# femto.net
KiCad netlist of a schematic drawn in EAGLE
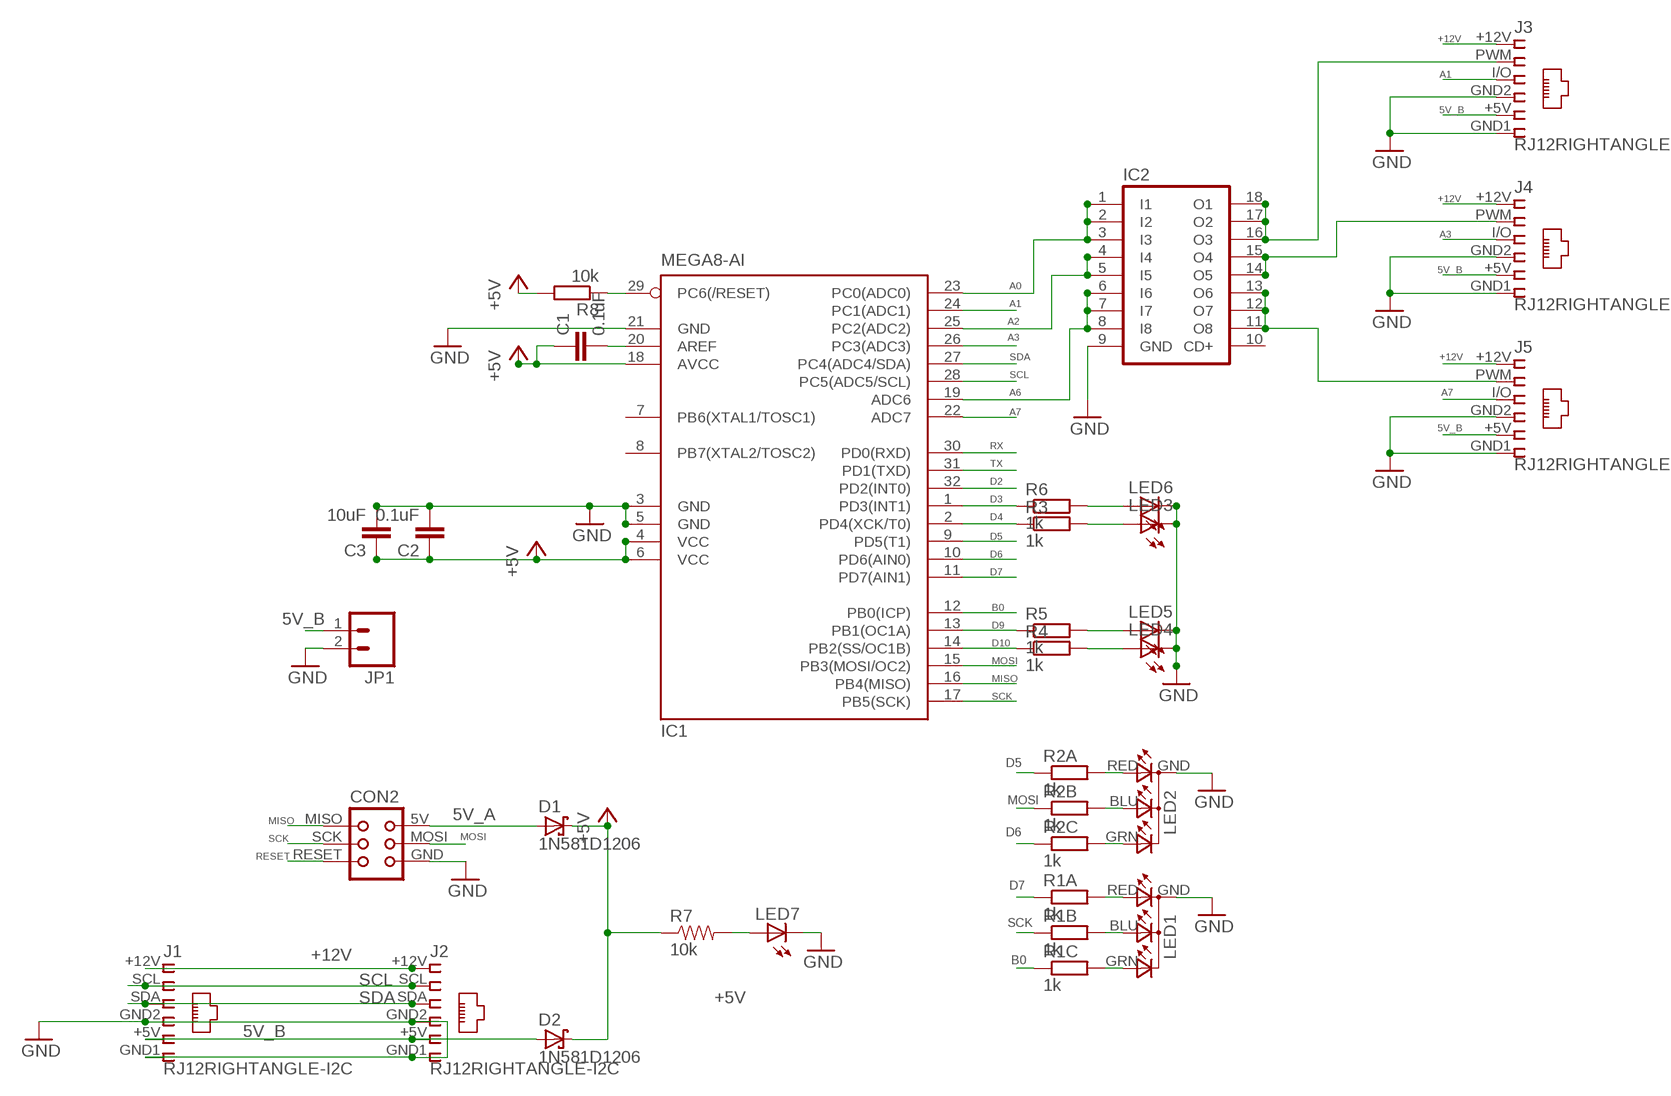
[diagram p0: schematic, sheet 1]

(export (version "E")
  (design (tool "Eeschema 10.0.6"))
  (components
    (comp (ref "C1")
      (value "0.1uF")
      (footprint "eagle-import:C1206")
      (libsource (lib "eagle-import") (part "C-EUC1206"))
    )
    (comp (ref "C2")
      (value "0.1uF")
      (footprint "eagle-import:C1206")
      (libsource (lib "eagle-import") (part "C-EUC1206"))
    )
    (comp (ref "C3")
      (value "10uF")
      (footprint "eagle-import:C1206")
      (libsource (lib "eagle-import") (part "C-EUC1206"))
    )
    (comp (ref "CON2")
      (value "TINYISPTAG")
      (footprint "eagle-import:TC2030-MCP")
      (libsource (lib "eagle-import") (part "TINYISPTAG"))
    )
    (comp (ref "D1")
      (value "1N581D1206")
      (footprint "eagle-import:LED-1206")
      (libsource (lib "eagle-import") (part "1N581D1206"))
    )
    (comp (ref "D2")
      (value "1N581D1206")
      (footprint "eagle-import:LED-1206")
      (libsource (lib "eagle-import") (part "1N581D1206"))
    )
    (comp (ref "IC1")
      (value "MEGA8-AI")
      (footprint "eagle-import:TQFP32-08")
      (fields (field (name "MPN") "ATMEGA8-16AU"))
      (libsource (lib "eagle-import") (part "MEGA8-AI"))
    )
    (comp (ref "IC2")
      (value "ULN2803A")
      (footprint "eagle-import:SO18W")
      (libsource (lib "eagle-import") (part "ULN2803A"))
    )
    (comp (ref "J1")
      (value "RJ12RIGHTANGLE-I2C")
      (footprint "eagle-import:RJ12-RIGHTANGLE-I2C")
      (libsource (lib "eagle-import") (part "RJ12RIGHTANGLE-I2C"))
    )
    (comp (ref "J2")
      (value "RJ12RIGHTANGLE-I2C")
      (footprint "eagle-import:RJ12-RIGHTANGLE-I2C")
      (libsource (lib "eagle-import") (part "RJ12RIGHTANGLE-I2C"))
    )
    (comp (ref "J3")
      (value "RJ12RIGHTANGLE")
      (footprint "eagle-import:RJ12-RIGHTANGLE")
      (libsource (lib "eagle-import") (part "RJ12RIGHTANGLE"))
    )
    (comp (ref "J4")
      (value "RJ12RIGHTANGLE")
      (footprint "eagle-import:RJ12-RIGHTANGLE")
      (libsource (lib "eagle-import") (part "RJ12RIGHTANGLE"))
    )
    (comp (ref "J5")
      (value "RJ12RIGHTANGLE")
      (footprint "eagle-import:RJ12-RIGHTANGLE")
      (libsource (lib "eagle-import") (part "RJ12RIGHTANGLE"))
    )
    (comp (ref "JP1")
      (value "M023.5MM")
      (footprint "eagle-import:SCREWTERMINAL-3.5MM-2")
      (libsource (lib "eagle-import") (part "M023.5MM"))
    )
    (comp (ref "LED1")
      (value "RGB-COMMON-CATHODE")
      (footprint "eagle-import:LED-TRICOLOR-THROUGHHOLE")
      (libsource (lib "eagle-import") (part "RGB-COMMON-CATHODE"))
    )
    (comp (ref "LED2")
      (value "RGB-COMMON-CATHODE")
      (footprint "eagle-import:LED-TRICOLOR-THROUGHHOLE")
      (libsource (lib "eagle-import") (part "RGB-COMMON-CATHODE"))
    )
    (comp (ref "LED3")
      (value "LED3MM")
      (footprint "eagle-import:LED3MM")
      (libsource (lib "eagle-import") (part "lpatiny_LED3MM"))
    )
    (comp (ref "LED4")
      (value "LED3MM")
      (footprint "eagle-import:LED3MM")
      (libsource (lib "eagle-import") (part "lpatiny_LED3MM"))
    )
    (comp (ref "LED5")
      (value "LED3MM")
      (footprint "eagle-import:LED3MM")
      (libsource (lib "eagle-import") (part "lpatiny_LED3MM"))
    )
    (comp (ref "LED6")
      (value "LED3MM")
      (footprint "eagle-import:LED3MM")
      (libsource (lib "eagle-import") (part "lpatiny_LED3MM"))
    )
    (comp (ref "LED7")
      (value "LEDCHIP-LED0603")
      (footprint "eagle-import:CHIP-LED0603")
      (libsource (lib "eagle-import") (part "LEDCHIP-LED0603"))
    )
    (comp (ref "R1A")
      (value "1k")
      (footprint "eagle-import:M1206")
      (libsource (lib "eagle-import") (part "R-EU_M1206"))
    )
    (comp (ref "R1B")
      (value "1k")
      (footprint "eagle-import:M1206")
      (libsource (lib "eagle-import") (part "R-EU_M1206"))
    )
    (comp (ref "R1C")
      (value "1k")
      (footprint "eagle-import:M1206")
      (libsource (lib "eagle-import") (part "R-EU_M1206"))
    )
    (comp (ref "R2A")
      (value "1k")
      (footprint "eagle-import:M1206")
      (libsource (lib "eagle-import") (part "R-EU_M1206"))
    )
    (comp (ref "R2B")
      (value "1k")
      (footprint "eagle-import:M1206")
      (libsource (lib "eagle-import") (part "R-EU_M1206"))
    )
    (comp (ref "R2C")
      (value "1k")
      (footprint "eagle-import:M1206")
      (libsource (lib "eagle-import") (part "R-EU_M1206"))
    )
    (comp (ref "R3")
      (value "1k")
      (footprint "eagle-import:M1206")
      (libsource (lib "eagle-import") (part "R-EU_M1206"))
    )
    (comp (ref "R4")
      (value "1k")
      (footprint "eagle-import:M1206")
      (libsource (lib "eagle-import") (part "R-EU_M1206"))
    )
    (comp (ref "R5")
      (value "1k")
      (footprint "eagle-import:M1206")
      (libsource (lib "eagle-import") (part "R-EU_M1206"))
    )
    (comp (ref "R6")
      (value "1k")
      (footprint "eagle-import:M1206")
      (libsource (lib "eagle-import") (part "R-EU_M1206"))
    )
    (comp (ref "R7")
      (value "10k")
      (footprint "eagle-import:0603-RES")
      (libsource (lib "eagle-import") (part "RESISTOR0603-RES"))
    )
    (comp (ref "R8")
      (value "10k")
      (footprint "eagle-import:M1206")
      (libsource (lib "eagle-import") (part "R-EU_M1206"))
    )
  )
  (nets
    (net (code "1") (name "+5V") (class "Default")
      (node (ref "C1") (pin "1") (pinfunction "1_1") (pintype "passive"))
      (node (ref "C2") (pin "1") (pinfunction "1_1") (pintype "passive"))
      (node (ref "C3") (pin "1") (pinfunction "1_1") (pintype "passive"))
      (node (ref "D1") (pin "C") (pinfunction "C_C") (pintype "passive"))
      (node (ref "D2") (pin "C") (pinfunction "C_C") (pintype "passive"))
      (node (ref "IC1") (pin "18") (pinfunction "AVCC_18") (pintype "power_in"))
      (node (ref "IC1") (pin "4") (pinfunction "VCC_4") (pintype "power_in"))
      (node (ref "IC1") (pin "6") (pinfunction "VCC_6") (pintype "power_in"))
      (node (ref "R7") (pin "1") (pinfunction "1_1") (pintype "passive"))
      (node (ref "R8") (pin "2") (pinfunction "2_2") (pintype "passive"))
    )
    (net (code "2") (name "/+12V") (class "Default")
      (node (ref "J1") (pin "+12V") (pinfunction "1_+12V") (pintype "bidirectional"))
      (node (ref "J2") (pin "+12V") (pinfunction "1_+12V") (pintype "bidirectional"))
      (node (ref "J3") (pin "+12V") (pinfunction "1_+12V") (pintype "bidirectional"))
      (node (ref "J4") (pin "+12V") (pinfunction "1_+12V") (pintype "bidirectional"))
      (node (ref "J5") (pin "+12V") (pinfunction "1_+12V") (pintype "bidirectional"))
    )
    (net (code "3") (name "/5V_A") (class "Default")
      (node (ref "CON2") (pin "5V") (pinfunction "VCC_5V") (pintype "passive"))
      (node (ref "D1") (pin "A") (pinfunction "A_A") (pintype "passive"))
    )
    (net (code "4") (name "/5V_B") (class "Default")
      (node (ref "D2") (pin "A") (pinfunction "A_A") (pintype "passive"))
      (node (ref "J1") (pin "+5V") (pinfunction "5_+5V") (pintype "bidirectional"))
      (node (ref "J2") (pin "+5V") (pinfunction "5_+5V") (pintype "bidirectional"))
      (node (ref "J3") (pin "+5V") (pinfunction "5_+5V") (pintype "bidirectional"))
      (node (ref "J4") (pin "+5V") (pinfunction "5_+5V") (pintype "bidirectional"))
      (node (ref "J5") (pin "+5V") (pinfunction "5_+5V") (pintype "bidirectional"))
      (node (ref "JP1") (pin "1") (pinfunction "1_1") (pintype "passive"))
    )
    (net (code "5") (name "/A0") (class "Default")
      (node (ref "IC1") (pin "23") (pinfunction "PC0(ADC0)_23") (pintype "bidirectional"))
      (node (ref "IC2") (pin "1") (pinfunction "I1_1") (pintype "input"))
      (node (ref "IC2") (pin "2") (pinfunction "I2_2") (pintype "input"))
      (node (ref "IC2") (pin "3") (pinfunction "I3_3") (pintype "input"))
    )
    (net (code "6") (name "/A1") (class "Default")
      (node (ref "IC1") (pin "24") (pinfunction "PC1(ADC1)_24") (pintype "bidirectional"))
      (node (ref "J3") (pin "I/O") (pinfunction "3_I/O") (pintype "bidirectional"))
    )
    (net (code "7") (name "/A2") (class "Default")
      (node (ref "IC1") (pin "25") (pinfunction "PC2(ADC2)_25") (pintype "bidirectional"))
      (node (ref "IC2") (pin "4") (pinfunction "I4_4") (pintype "input"))
      (node (ref "IC2") (pin "5") (pinfunction "I5_5") (pintype "input"))
    )
    (net (code "8") (name "/A3") (class "Default")
      (node (ref "IC1") (pin "26") (pinfunction "PC3(ADC3)_26") (pintype "bidirectional"))
      (node (ref "J4") (pin "I/O") (pinfunction "3_I/O") (pintype "bidirectional"))
    )
    (net (code "9") (name "/A6") (class "Default")
      (node (ref "IC1") (pin "19") (pinfunction "ADC6_19") (pintype "bidirectional"))
      (node (ref "IC2") (pin "6") (pinfunction "I6_6") (pintype "input"))
      (node (ref "IC2") (pin "7") (pinfunction "I7_7") (pintype "input"))
      (node (ref "IC2") (pin "8") (pinfunction "I8_8") (pintype "input"))
    )
    (net (code "10") (name "/A7") (class "Default")
      (node (ref "IC1") (pin "22") (pinfunction "ADC7_22") (pintype "bidirectional"))
      (node (ref "J5") (pin "I/O") (pinfunction "3_I/O") (pintype "bidirectional"))
    )
    (net (code "11") (name "/B0") (class "Default")
      (node (ref "IC1") (pin "12") (pinfunction "PB0(ICP)_12") (pintype "bidirectional"))
      (node (ref "R1C") (pin "1") (pinfunction "1_1") (pintype "passive"))
    )
    (net (code "12") (name "/D2") (class "Default")
      (node (ref "IC1") (pin "32") (pinfunction "PD2(INT0)_32") (pintype "bidirectional"))
    )
    (net (code "13") (name "/D3") (class "Default")
      (node (ref "IC1") (pin "1") (pinfunction "PD3(INT1)_1") (pintype "bidirectional"))
      (node (ref "R6") (pin "1") (pinfunction "1_1") (pintype "passive"))
    )
    (net (code "14") (name "/D4") (class "Default")
      (node (ref "IC1") (pin "2") (pinfunction "PD4(XCK/T0)_2") (pintype "bidirectional"))
      (node (ref "R3") (pin "1") (pinfunction "1_1") (pintype "passive"))
    )
    (net (code "15") (name "/D5") (class "Default")
      (node (ref "IC1") (pin "9") (pinfunction "PD5(T1)_9") (pintype "bidirectional"))
      (node (ref "R2A") (pin "1") (pinfunction "1_1") (pintype "passive"))
    )
    (net (code "16") (name "/D6") (class "Default")
      (node (ref "IC1") (pin "10") (pinfunction "PD6(AIN0)_10") (pintype "bidirectional"))
      (node (ref "R2C") (pin "1") (pinfunction "1_1") (pintype "passive"))
    )
    (net (code "17") (name "/D7") (class "Default")
      (node (ref "IC1") (pin "11") (pinfunction "PD7(AIN1)_11") (pintype "bidirectional"))
      (node (ref "R1A") (pin "1") (pinfunction "1_1") (pintype "passive"))
    )
    (net (code "18") (name "/D9") (class "Default")
      (node (ref "IC1") (pin "13") (pinfunction "PB1(OC1A)_13") (pintype "bidirectional"))
      (node (ref "R5") (pin "1") (pinfunction "1_1") (pintype "passive"))
    )
    (net (code "19") (name "/D10") (class "Default")
      (node (ref "IC1") (pin "14") (pinfunction "PB2(SS/OC1B)_14") (pintype "bidirectional"))
      (node (ref "R4") (pin "1") (pinfunction "1_1") (pintype "passive"))
    )
    (net (code "20") (name "/MISO") (class "Default")
      (node (ref "CON2") (pin "MISO") (pinfunction "MISO_MISO") (pintype "passive"))
      (node (ref "IC1") (pin "16") (pinfunction "PB4(MISO)_16") (pintype "bidirectional"))
    )
    (net (code "21") (name "/MOSI") (class "Default")
      (node (ref "CON2") (pin "MOSI") (pinfunction "MOSI_MOSI") (pintype "passive"))
      (node (ref "IC1") (pin "15") (pinfunction "PB3(MOSI/OC2)_15") (pintype "bidirectional"))
      (node (ref "R2B") (pin "1") (pinfunction "1_1") (pintype "passive"))
    )
    (net (code "22") (name "/RESET") (class "Default")
      (node (ref "CON2") (pin "RESET") (pinfunction "RESET_RESET") (pintype "passive"))
      (node (ref "IC1") (pin "29") (pinfunction "PC6(/RESET)_29") (pintype "bidirectional"))
      (node (ref "R8") (pin "1") (pinfunction "1_1") (pintype "passive"))
    )
    (net (code "23") (name "/RX") (class "Default")
      (node (ref "IC1") (pin "30") (pinfunction "PD0(RXD)_30") (pintype "bidirectional"))
    )
    (net (code "24") (name "/SCK") (class "Default")
      (node (ref "CON2") (pin "SCK") (pinfunction "SCK_SCK") (pintype "passive"))
      (node (ref "IC1") (pin "17") (pinfunction "PB5(SCK)_17") (pintype "bidirectional"))
      (node (ref "R1B") (pin "1") (pinfunction "1_1") (pintype "passive"))
    )
    (net (code "25") (name "/SCL") (class "Default")
      (node (ref "IC1") (pin "28") (pinfunction "PC5(ADC5/SCL)_28") (pintype "bidirectional"))
      (node (ref "J1") (pin "SCL") (pinfunction "2_SCL") (pintype "bidirectional"))
      (node (ref "J2") (pin "SCL") (pinfunction "2_SCL") (pintype "bidirectional"))
    )
    (net (code "26") (name "/SDA") (class "Default")
      (node (ref "IC1") (pin "27") (pinfunction "PC4(ADC4/SDA)_27") (pintype "bidirectional"))
      (node (ref "J1") (pin "SDA") (pinfunction "3_SDA") (pintype "bidirectional"))
      (node (ref "J2") (pin "SDA") (pinfunction "3_SDA") (pintype "bidirectional"))
    )
    (net (code "27") (name "/TX") (class "Default")
      (node (ref "IC1") (pin "31") (pinfunction "PD1(TXD)_31") (pintype "bidirectional"))
    )
    (net (code "28") (name "GND") (class "Default")
      (node (ref "C2") (pin "2") (pinfunction "2_2") (pintype "passive"))
      (node (ref "C3") (pin "2") (pinfunction "2_2") (pintype "passive"))
      (node (ref "CON2") (pin "GND") (pinfunction "GND_GND") (pintype "passive"))
      (node (ref "IC1") (pin "21") (pinfunction "GND_21") (pintype "power_in"))
      (node (ref "IC1") (pin "3") (pinfunction "GND_3") (pintype "power_in"))
      (node (ref "IC1") (pin "5") (pinfunction "GND_5") (pintype "power_in"))
      (node (ref "IC2") (pin "9") (pinfunction "GND_9") (pintype "power_in"))
      (node (ref "J1") (pin "GND1") (pinfunction "6_GND1") (pintype "bidirectional"))
      (node (ref "J1") (pin "GND2") (pinfunction "4_GND2") (pintype "bidirectional"))
      (node (ref "J2") (pin "GND1") (pinfunction "6_GND1") (pintype "bidirectional"))
      (node (ref "J2") (pin "GND2") (pinfunction "4_GND2") (pintype "bidirectional"))
      (node (ref "J3") (pin "GND1") (pinfunction "6_GND1") (pintype "bidirectional"))
      (node (ref "J3") (pin "GND2") (pinfunction "4_GND2") (pintype "bidirectional"))
      (node (ref "J4") (pin "GND1") (pinfunction "6_GND1") (pintype "bidirectional"))
      (node (ref "J4") (pin "GND2") (pinfunction "4_GND2") (pintype "bidirectional"))
      (node (ref "J5") (pin "GND1") (pinfunction "6_GND1") (pintype "bidirectional"))
      (node (ref "J5") (pin "GND2") (pinfunction "4_GND2") (pintype "bidirectional"))
      (node (ref "JP1") (pin "2") (pinfunction "2_2") (pintype "passive"))
      (node (ref "LED1") (pin "GND") (pinfunction "A2_GND") (pintype "passive"))
      (node (ref "LED2") (pin "GND") (pinfunction "A2_GND") (pintype "passive"))
      (node (ref "LED3") (pin "K") (pinfunction "C_K") (pintype "passive"))
      (node (ref "LED4") (pin "K") (pinfunction "C_K") (pintype "passive"))
      (node (ref "LED5") (pin "K") (pinfunction "C_K") (pintype "passive"))
      (node (ref "LED6") (pin "K") (pinfunction "C_K") (pintype "passive"))
      (node (ref "LED7") (pin "C") (pinfunction "C_C") (pintype "passive"))
    )
    (net (code "29") (name "Net-(IC1-AREF)") (class "Default")
      (node (ref "C1") (pin "2") (pinfunction "2_2") (pintype "passive"))
      (node (ref "IC1") (pin "20") (pinfunction "AREF_20") (pintype "passive"))
    )
    (net (code "30") (name "Net-(IC2-O1)") (class "Default")
      (node (ref "IC2") (pin "16") (pinfunction "O3_16") (pintype "open_collector"))
      (node (ref "IC2") (pin "17") (pinfunction "O2_17") (pintype "open_collector"))
      (node (ref "IC2") (pin "18") (pinfunction "O1_18") (pintype "open_collector"))
      (node (ref "J3") (pin "PWM") (pinfunction "2_PWM") (pintype "bidirectional"))
    )
    (net (code "31") (name "Net-(IC2-O4)") (class "Default")
      (node (ref "IC2") (pin "14") (pinfunction "O5_14") (pintype "open_collector"))
      (node (ref "IC2") (pin "15") (pinfunction "O4_15") (pintype "open_collector"))
      (node (ref "J4") (pin "PWM") (pinfunction "2_PWM") (pintype "bidirectional"))
    )
    (net (code "32") (name "Net-(IC2-O6)") (class "Default")
      (node (ref "IC2") (pin "11") (pinfunction "O8_11") (pintype "open_collector"))
      (node (ref "IC2") (pin "12") (pinfunction "O7_12") (pintype "open_collector"))
      (node (ref "IC2") (pin "13") (pinfunction "O6_13") (pintype "open_collector"))
      (node (ref "J5") (pin "PWM") (pinfunction "2_PWM") (pintype "bidirectional"))
    )
    (net (code "33") (name "Net-(LED1-CBLUE)") (class "Default")
      (node (ref "LED1") (pin "BLU") (pinfunction "CBLUE_BLU") (pintype "passive"))
      (node (ref "R1B") (pin "2") (pinfunction "2_2") (pintype "passive"))
    )
    (net (code "34") (name "Net-(LED1-CGREEN)") (class "Default")
      (node (ref "LED1") (pin "GRN") (pinfunction "CGREEN_GRN") (pintype "passive"))
      (node (ref "R1C") (pin "2") (pinfunction "2_2") (pintype "passive"))
    )
    (net (code "35") (name "Net-(LED1-CRED)") (class "Default")
      (node (ref "LED1") (pin "RED") (pinfunction "CRED_RED") (pintype "passive"))
      (node (ref "R1A") (pin "2") (pinfunction "2_2") (pintype "passive"))
    )
    (net (code "36") (name "Net-(LED2-CBLUE)") (class "Default")
      (node (ref "LED2") (pin "BLU") (pinfunction "CBLUE_BLU") (pintype "passive"))
      (node (ref "R2B") (pin "2") (pinfunction "2_2") (pintype "passive"))
    )
    (net (code "37") (name "Net-(LED2-CGREEN)") (class "Default")
      (node (ref "LED2") (pin "GRN") (pinfunction "CGREEN_GRN") (pintype "passive"))
      (node (ref "R2C") (pin "2") (pinfunction "2_2") (pintype "passive"))
    )
    (net (code "38") (name "Net-(LED2-CRED)") (class "Default")
      (node (ref "LED2") (pin "RED") (pinfunction "CRED_RED") (pintype "passive"))
      (node (ref "R2A") (pin "2") (pinfunction "2_2") (pintype "passive"))
    )
    (net (code "39") (name "Net-(LED3-PadA)") (class "Default")
      (node (ref "LED3") (pin "A") (pinfunction "A_A") (pintype "passive"))
      (node (ref "R3") (pin "2") (pinfunction "2_2") (pintype "passive"))
    )
    (net (code "40") (name "Net-(LED4-PadA)") (class "Default")
      (node (ref "LED4") (pin "A") (pinfunction "A_A") (pintype "passive"))
      (node (ref "R4") (pin "2") (pinfunction "2_2") (pintype "passive"))
    )
    (net (code "41") (name "Net-(LED5-PadA)") (class "Default")
      (node (ref "LED5") (pin "A") (pinfunction "A_A") (pintype "passive"))
      (node (ref "R5") (pin "2") (pinfunction "2_2") (pintype "passive"))
    )
    (net (code "42") (name "Net-(LED6-PadA)") (class "Default")
      (node (ref "LED6") (pin "A") (pinfunction "A_A") (pintype "passive"))
      (node (ref "R6") (pin "2") (pinfunction "2_2") (pintype "passive"))
    )
    (net (code "43") (name "Net-(LED7-PadA)") (class "Default")
      (node (ref "LED7") (pin "A") (pinfunction "A_A") (pintype "passive"))
      (node (ref "R7") (pin "2") (pinfunction "2_2") (pintype "passive"))
    )
    (net (code "44") (name "unconnected-(IC1-PB6(XTAL1{slash}TOSC1)-Pad7)") (class "Default")
      (node (ref "IC1") (pin "7") (pinfunction "PB6(XTAL1/TOSC1)_7") (pintype "bidirectional"))
    )
    (net (code "45") (name "unconnected-(IC1-PB7(XTAL2{slash}TOSC2)-Pad8)") (class "Default")
      (node (ref "IC1") (pin "8") (pinfunction "PB7(XTAL2/TOSC2)_8") (pintype "bidirectional"))
    )
    (net (code "46") (name "unconnected-(IC2-CD+-Pad10)") (class "Default")
      (node (ref "IC2") (pin "10") (pinfunction "CD+_10") (pintype "passive"))
    )
  )
)
